# esp_ikea_bekant_control.net
KiCad netlist of a schematic drawn in EAGLE
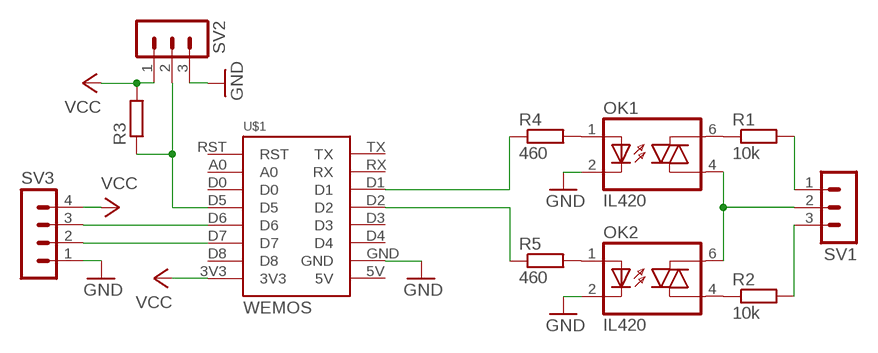
[diagram p0: schematic, sheet 1]

(export (version "E")
  (design (tool "Eeschema 10.0.6"))
  (components
    (comp (ref "OK1")
      (value "IL420")
      (footprint "eagle-import:DIL06")
      (fields (field (name "MF") "VISHAY/TELEFUNKEN"))
      (libsource (lib "eagle-import") (part "IL420"))
    )
    (comp (ref "OK2")
      (value "IL420")
      (footprint "eagle-import:DIL06")
      (fields (field (name "MF") "VISHAY/TELEFUNKEN"))
      (libsource (lib "eagle-import") (part "IL420"))
    )
    (comp (ref "R1")
      (value "10k")
      (footprint "eagle-import:0204_7")
      (libsource (lib "eagle-import") (part "R-EU_0204/7"))
    )
    (comp (ref "R2")
      (value "10k")
      (footprint "eagle-import:0204_7")
      (libsource (lib "eagle-import") (part "R-EU_0204/7"))
    )
    (comp (ref "R3")
      (value "R-EU_0204/7")
      (footprint "eagle-import:0204_7")
      (libsource (lib "eagle-import") (part "R-EU_0204/7"))
    )
    (comp (ref "R4")
      (value "460")
      (footprint "eagle-import:0204_7")
      (libsource (lib "eagle-import") (part "R-EU_0204/7"))
    )
    (comp (ref "R5")
      (value "460")
      (footprint "eagle-import:0204_7")
      (libsource (lib "eagle-import") (part "R-EU_0204/7"))
    )
    (comp (ref "SV1")
      (value "MA03-1")
      (footprint "eagle-import:MA03-1")
      (libsource (lib "eagle-import") (part "MA03-1"))
    )
    (comp (ref "SV2")
      (value "MA03-1")
      (footprint "eagle-import:MA03-1")
      (libsource (lib "eagle-import") (part "MA03-1"))
    )
    (comp (ref "SV3")
      (value "MA04-1")
      (footprint "eagle-import:MA04-1")
      (libsource (lib "eagle-import") (part "MA04-1"))
    )
    (comp (ref "U$1")
      (value "WEMOS")
      (footprint "eagle-import:WEMOS")
      (libsource (lib "eagle-import") (part "WEMOS"))
    )
  )
  (nets
    (net (code "1") (name "GND") (class "Default")
      (node (ref "OK1") (pin "2") (pinfunction "C_2") (pintype "passive"))
      (node (ref "OK2") (pin "2") (pinfunction "C_2") (pintype "passive"))
      (node (ref "SV2") (pin "3") (pinfunction "3_3") (pintype "passive"))
      (node (ref "SV3") (pin "1") (pinfunction "1_1") (pintype "passive"))
      (node (ref "U$1") (pin "GND") (pinfunction "GND_GND") (pintype "bidirectional"))
    )
    (net (code "2") (name "Net-(OK1-A)") (class "Default")
      (node (ref "OK1") (pin "1") (pinfunction "A_1") (pintype "passive"))
      (node (ref "R4") (pin "2") (pinfunction "2_2") (pintype "passive"))
    )
    (net (code "3") (name "Net-(OK1-A1)") (class "Default")
      (node (ref "OK1") (pin "4") (pinfunction "A1_4") (pintype "passive"))
      (node (ref "OK2") (pin "6") (pinfunction "A2_6") (pintype "passive"))
      (node (ref "SV1") (pin "2") (pinfunction "2_2") (pintype "passive"))
    )
    (net (code "4") (name "Net-(OK1-A2)") (class "Default")
      (node (ref "OK1") (pin "6") (pinfunction "A2_6") (pintype "passive"))
      (node (ref "R1") (pin "1") (pinfunction "1_1") (pintype "passive"))
    )
    (net (code "5") (name "Net-(OK2-A)") (class "Default")
      (node (ref "OK2") (pin "1") (pinfunction "A_1") (pintype "passive"))
      (node (ref "R5") (pin "2") (pinfunction "2_2") (pintype "passive"))
    )
    (net (code "6") (name "Net-(OK2-A1)") (class "Default")
      (node (ref "OK2") (pin "4") (pinfunction "A1_4") (pintype "passive"))
      (node (ref "R2") (pin "1") (pinfunction "1_1") (pintype "passive"))
    )
    (net (code "7") (name "Net-(R1-Pad2)") (class "Default")
      (node (ref "R1") (pin "2") (pinfunction "2_2") (pintype "passive"))
      (node (ref "SV1") (pin "1") (pinfunction "1_1") (pintype "passive"))
    )
    (net (code "8") (name "Net-(R2-Pad2)") (class "Default")
      (node (ref "R2") (pin "2") (pinfunction "2_2") (pintype "passive"))
      (node (ref "SV1") (pin "3") (pinfunction "3_3") (pintype "passive"))
    )
    (net (code "9") (name "Net-(R3-Pad1)") (class "Default")
      (node (ref "R3") (pin "1") (pinfunction "1_1") (pintype "passive"))
      (node (ref "SV2") (pin "2") (pinfunction "2_2") (pintype "passive"))
      (node (ref "U$1") (pin "D5") (pinfunction "D5_D5") (pintype "bidirectional"))
    )
    (net (code "10") (name "Net-(R4-Pad1)") (class "Default")
      (node (ref "R4") (pin "1") (pinfunction "1_1") (pintype "passive"))
      (node (ref "U$1") (pin "D1") (pinfunction "D1_D1") (pintype "bidirectional"))
    )
    (net (code "11") (name "Net-(R5-Pad1)") (class "Default")
      (node (ref "R5") (pin "1") (pinfunction "1_1") (pintype "passive"))
      (node (ref "U$1") (pin "D2") (pinfunction "D2_D2") (pintype "bidirectional"))
    )
    (net (code "12") (name "Net-(SV3-Pad2)") (class "Default")
      (node (ref "SV3") (pin "2") (pinfunction "2_2") (pintype "passive"))
      (node (ref "U$1") (pin "D7") (pinfunction "D7_D7") (pintype "bidirectional"))
    )
    (net (code "13") (name "Net-(SV3-Pad3)") (class "Default")
      (node (ref "SV3") (pin "3") (pinfunction "3_3") (pintype "passive"))
      (node (ref "U$1") (pin "D6") (pinfunction "D6_D6") (pintype "bidirectional"))
    )
    (net (code "14") (name "VCC") (class "Default")
      (node (ref "R3") (pin "2") (pinfunction "2_2") (pintype "passive"))
      (node (ref "SV2") (pin "1") (pinfunction "1_1") (pintype "passive"))
      (node (ref "SV3") (pin "4") (pinfunction "4_4") (pintype "passive"))
      (node (ref "U$1") (pin "3V3") (pinfunction "3V3_3V3") (pintype "bidirectional"))
    )
    (net (code "15") (name "unconnected-(U$1-Pad5V)") (class "Default")
      (node (ref "U$1") (pin "5V") (pinfunction "5V_5V") (pintype "bidirectional"))
    )
    (net (code "16") (name "unconnected-(U$1-PadA0)") (class "Default")
      (node (ref "U$1") (pin "A0") (pinfunction "A0_A0") (pintype "bidirectional"))
    )
    (net (code "17") (name "unconnected-(U$1-PadD0)") (class "Default")
      (node (ref "U$1") (pin "D0") (pinfunction "D0_D0") (pintype "bidirectional"))
    )
    (net (code "18") (name "unconnected-(U$1-PadD3)") (class "Default")
      (node (ref "U$1") (pin "D3") (pinfunction "D3_D3") (pintype "bidirectional"))
    )
    (net (code "19") (name "unconnected-(U$1-PadD4)") (class "Default")
      (node (ref "U$1") (pin "D4") (pinfunction "D4_D4") (pintype "bidirectional"))
    )
    (net (code "20") (name "unconnected-(U$1-PadD8)") (class "Default")
      (node (ref "U$1") (pin "D8") (pinfunction "D8_D8") (pintype "bidirectional"))
    )
    (net (code "21") (name "unconnected-(U$1-PadRST)") (class "Default")
      (node (ref "U$1") (pin "RST") (pinfunction "RST_RST") (pintype "bidirectional"))
    )
    (net (code "22") (name "unconnected-(U$1-PadRX)") (class "Default")
      (node (ref "U$1") (pin "RX") (pinfunction "RX_RX") (pintype "bidirectional"))
    )
    (net (code "23") (name "unconnected-(U$1-PadTX)") (class "Default")
      (node (ref "U$1") (pin "TX") (pinfunction "TX_TX") (pintype "bidirectional"))
    )
  )
)
